# 03_mcu_display.net
KiCad netlist of a schematic drawn in Altium Designer
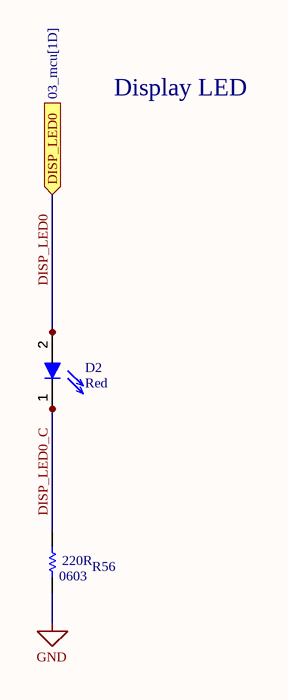
[diagram p0: 03_mcu_display.SchDoc]

(export (version "E")
  (design (tool "Eeschema 10.0.6"))
  (components
    (comp (ref "D2")
      (value "Red")
      (footprint "DISPLAY-LED")
      (description "LED RED CLEAR 0603 SMD")
      (fields
        (field (name "MANUFACTURER") "Vishay Lite-On")
        (field (name "MANUFACTURER PART NUMBER") "LTST-C191KRKT")
      )
      (libsource (lib "tcspc00") (part "LTST-C191KRKT"))
    )
    (comp (ref "R56")
      (value "RMCF0603JT220R")
      (footprint "RES-STACK-POLE-0603")
      (description "RES 220 OHM 5% 1/10W 0603")
      (libsource (lib "tcspc00") (part "RMCF0603JT220R"))
    )
  )
  (nets
    (net (code "1") (name "/DISP_LED0") (class "Default") (node (ref "D2") (pin "2") (pintype "passive")))
    (net (code "2") (name "/DISP_LED0_C") (class "Default")
      (node (ref "D2") (pin "1") (pintype "passive"))
      (node (ref "R56") (pin "2") (pinfunction "2_2") (pintype "passive"))
    )
    (net (code "3") (name "GND") (class "Default")
      (node (ref "R56") (pin "1") (pinfunction "1_1") (pintype "passive"))
    )
  )
)
